# M3005.net
KiCad netlist of a schematic drawn in Altium Designer
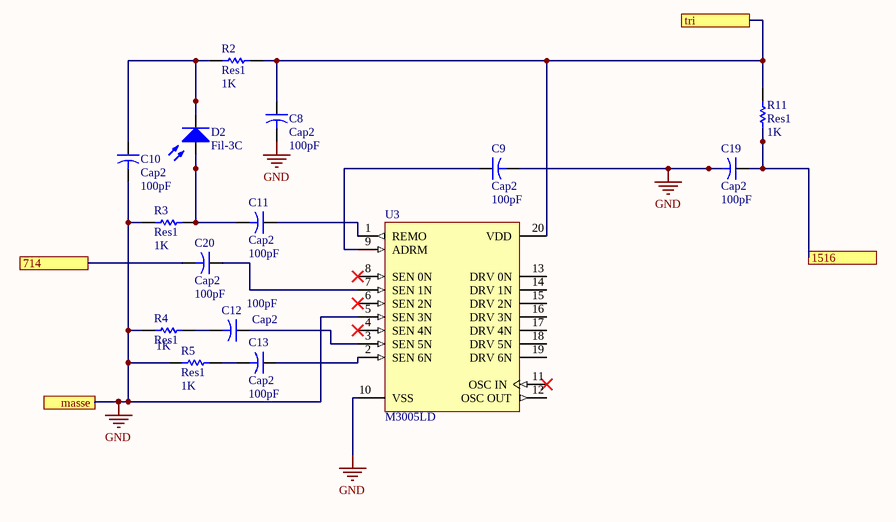
[diagram p0: M3005.SchDoc]

(export (version "E")
  (design (tool "Eeschema 10.0.6"))
  (components
    (comp (ref "C8")
      (value "Cap2")
      (footprint "RAD-0.2")
      (description "Capacitor")
      (fields (field (name "ALTIUM_VALUE") "100pF") (field (name "PUBLISHER") "Altium Limited"))
      (libsource (lib "Miscellaneous Devices") (part "Cap2"))
    )
    (comp (ref "C9")
      (value "Cap2")
      (footprint "RAD-0.2")
      (description "Capacitor")
      (fields (field (name "ALTIUM_VALUE") "100pF") (field (name "PUBLISHER") "Altium Limited"))
      (libsource (lib "Miscellaneous Devices") (part "Cap2"))
    )
    (comp (ref "C10")
      (value "Cap2")
      (footprint "RAD-0.2")
      (description "Capacitor")
      (fields (field (name "ALTIUM_VALUE") "100pF") (field (name "PUBLISHER") "Altium Limited"))
      (libsource (lib "Miscellaneous Devices") (part "Cap2"))
    )
    (comp (ref "C11")
      (value "Cap2")
      (footprint "RAD-0.2")
      (description "Capacitor")
      (fields (field (name "ALTIUM_VALUE") "100pF") (field (name "PUBLISHER") "Altium Limited"))
      (libsource (lib "Miscellaneous Devices") (part "Cap2"))
    )
    (comp (ref "C12")
      (value "Cap2")
      (footprint "RAD-0.2")
      (description "Capacitor")
      (fields (field (name "ALTIUM_VALUE") "100pF") (field (name "PUBLISHER") "Altium Limited"))
      (libsource (lib "Miscellaneous Devices") (part "Cap2"))
    )
    (comp (ref "C13")
      (value "Cap2")
      (footprint "RAD-0.2")
      (description "Capacitor")
      (fields (field (name "ALTIUM_VALUE") "100pF") (field (name "PUBLISHER") "Altium Limited"))
      (libsource (lib "Miscellaneous Devices") (part "Cap2"))
    )
    (comp (ref "C19")
      (value "Cap2")
      (footprint "RAD-0.2")
      (description "Capacitor")
      (fields (field (name "ALTIUM_VALUE") "100pF") (field (name "PUBLISHER") "Altium Limited"))
      (libsource (lib "Miscellaneous Devices") (part "Cap2"))
    )
    (comp (ref "C20")
      (value "Cap2")
      (footprint "RAD-0.2")
      (description "Capacitor")
      (fields (field (name "ALTIUM_VALUE") "100pF") (field (name "PUBLISHER") "Altium Limited"))
      (libsource (lib "Miscellaneous Devices") (part "Cap2"))
    )
    (comp (ref "D2")
      (value "Fil-3C")
      (footprint "PIN2")
      (description "Photosensitive Diode")
      (fields (field (name "PUBLISHER") "Altium Limited"))
      (libsource (lib "Miscellaneous Devices") (part "Photo Sen"))
    )
    (comp (ref "R2")
      (value "Res1")
      (footprint "AXIAL-0.3")
      (description "Resistor")
      (fields (field (name "ALTIUM_VALUE") "1K") (field (name "PUBLISHER") "Altium Limited"))
      (libsource (lib "Miscellaneous Devices") (part "Res1"))
    )
    (comp (ref "R3")
      (value "Res1")
      (footprint "AXIAL-0.3")
      (description "Resistor")
      (fields (field (name "ALTIUM_VALUE") "1K") (field (name "PUBLISHER") "Altium Limited"))
      (libsource (lib "Miscellaneous Devices") (part "Res1"))
    )
    (comp (ref "R4")
      (value "Res1")
      (footprint "AXIAL-0.3")
      (description "Resistor")
      (fields (field (name "ALTIUM_VALUE") "1K") (field (name "PUBLISHER") "Altium Limited"))
      (libsource (lib "Miscellaneous Devices") (part "Res1"))
    )
    (comp (ref "R5")
      (value "Res1")
      (footprint "AXIAL-0.3")
      (description "Resistor")
      (fields (field (name "ALTIUM_VALUE") "1K") (field (name "PUBLISHER") "Altium Limited"))
      (libsource (lib "Miscellaneous Devices") (part "Res1"))
    )
    (comp (ref "R11")
      (value "Res1")
      (footprint "AXIAL-0.3")
      (description "Resistor")
      (fields (field (name "ALTIUM_VALUE") "1K") (field (name "PUBLISHER") "Altium Limited"))
      (libsource (lib "Miscellaneous Devices") (part "Res1"))
    )
    (comp (ref "U3")
      (value "M3005LD")
      (footprint "SO20_N")
      (description "Remote Control Transmitter")
      (fields (field (name "PUBLISHER") "Altium Limited"))
      (libsource (lib "ST Remote Control Transmitter") (part "M3005LD"))
    )
  )
  (nets
    (net (code "1") (name "/714") (class "Default")
      (node (ref "C20") (pin "2") (pinfunction "2_2") (pintype "passive"))
    )
    (net (code "2") (name "/1516") (class "Default")
      (node (ref "C19") (pin "1") (pinfunction "1_1") (pintype "passive"))
      (node (ref "R11") (pin "1") (pinfunction "1_1") (pintype "passive"))
    )
    (net (code "3") (name "/tri") (class "Default")
      (node (ref "C8") (pin "1") (pinfunction "1_1") (pintype "passive"))
      (node (ref "R11") (pin "2") (pinfunction "2_2") (pintype "passive"))
      (node (ref "R2") (pin "1") (pinfunction "1_1") (pintype "passive"))
      (node (ref "U3") (pin "20") (pinfunction "VDD_20") (pintype "power_in"))
    )
    (net (code "4") (name "GND") (class "Default")
      (node (ref "C10") (pin "2") (pinfunction "2_2") (pintype "passive"))
      (node (ref "C19") (pin "2") (pinfunction "2_2") (pintype "passive"))
      (node (ref "C8") (pin "2") (pinfunction "2_2") (pintype "passive"))
      (node (ref "C9") (pin "2") (pinfunction "2_2") (pintype "passive"))
      (node (ref "R3") (pin "1") (pinfunction "1_1") (pintype "passive"))
      (node (ref "R4") (pin "1") (pinfunction "1_1") (pintype "passive"))
      (node (ref "R5") (pin "1") (pinfunction "1_1") (pintype "passive"))
      (node (ref "U3") (pin "10") (pinfunction "VSS_10") (pintype "power_in"))
      (node (ref "U3") (pin "5") (pinfunction "SEN_3N_5") (pintype "input"))
    )
    (net (code "5") (name "Net-(C12-Pad2)") (class "Default")
      (node (ref "C12") (pin "2") (pinfunction "2_2") (pintype "passive"))
      (node (ref "R4") (pin "2") (pinfunction "2_2") (pintype "passive"))
    )
    (net (code "6") (name "Net-(C13-Pad2)") (class "Default")
      (node (ref "C13") (pin "2") (pinfunction "2_2") (pintype "passive"))
      (node (ref "R5") (pin "2") (pinfunction "2_2") (pintype "passive"))
    )
    (net (code "7") (name "Net-(D2-A)") (class "Default")
      (node (ref "C11") (pin "2") (pinfunction "2_2") (pintype "passive"))
      (node (ref "D2") (pin "1") (pinfunction "A_1") (pintype "passive"))
      (node (ref "R3") (pin "2") (pinfunction "2_2") (pintype "passive"))
    )
    (net (code "8") (name "Net-(D2-K)") (class "Default")
      (node (ref "C10") (pin "1") (pinfunction "1_1") (pintype "passive"))
      (node (ref "D2") (pin "2") (pinfunction "K_2") (pintype "passive"))
      (node (ref "R2") (pin "2") (pinfunction "2_2") (pintype "passive"))
    )
    (net (code "9") (name "Net-(U3-ADRM)") (class "Default")
      (node (ref "C9") (pin "1") (pinfunction "1_1") (pintype "passive"))
      (node (ref "U3") (pin "9") (pinfunction "ADRM_9") (pintype "input"))
    )
    (net (code "10") (name "Net-(U3-REMO)") (class "Default")
      (node (ref "C11") (pin "1") (pinfunction "1_1") (pintype "passive"))
      (node (ref "U3") (pin "1") (pinfunction "REMO_1") (pintype "output"))
    )
    (net (code "11") (name "Net-(U3-SEN_1N)") (class "Default")
      (node (ref "C20") (pin "1") (pinfunction "1_1") (pintype "passive"))
      (node (ref "U3") (pin "7") (pinfunction "SEN_1N_7") (pintype "input"))
    )
    (net (code "12") (name "Net-(U3-SEN_5N)") (class "Default")
      (node (ref "C12") (pin "1") (pinfunction "1_1") (pintype "passive"))
      (node (ref "U3") (pin "3") (pinfunction "SEN_5N_3") (pintype "input"))
    )
    (net (code "13") (name "Net-(U3-SEN_6N)") (class "Default")
      (node (ref "C13") (pin "1") (pinfunction "1_1") (pintype "passive"))
      (node (ref "U3") (pin "2") (pinfunction "SEN_6N_2") (pintype "input"))
    )
    (net (code "14") (name "unconnected-(U3-DRV_0N-Pad13)") (class "Default")
      (node (ref "U3") (pin "13") (pinfunction "DRV_0N_13") (pintype "open_collector"))
    )
    (net (code "15") (name "unconnected-(U3-DRV_1N-Pad14)") (class "Default")
      (node (ref "U3") (pin "14") (pinfunction "DRV_1N_14") (pintype "open_collector"))
    )
    (net (code "16") (name "unconnected-(U3-DRV_2N-Pad15)") (class "Default")
      (node (ref "U3") (pin "15") (pinfunction "DRV_2N_15") (pintype "open_collector"))
    )
    (net (code "17") (name "unconnected-(U3-DRV_3N-Pad16)") (class "Default")
      (node (ref "U3") (pin "16") (pinfunction "DRV_3N_16") (pintype "open_collector"))
    )
    (net (code "18") (name "unconnected-(U3-DRV_4N-Pad17)") (class "Default")
      (node (ref "U3") (pin "17") (pinfunction "DRV_4N_17") (pintype "open_collector"))
    )
    (net (code "19") (name "unconnected-(U3-DRV_5N-Pad18)") (class "Default")
      (node (ref "U3") (pin "18") (pinfunction "DRV_5N_18") (pintype "open_collector"))
    )
    (net (code "20") (name "unconnected-(U3-DRV_6N-Pad19)") (class "Default")
      (node (ref "U3") (pin "19") (pinfunction "DRV_6N_19") (pintype "open_collector"))
    )
    (net (code "21") (name "unconnected-(U3-OSC_IN-Pad11)") (class "Default")
      (node (ref "U3") (pin "11") (pinfunction "OSC_IN_11") (pintype "input+no_connect"))
    )
    (net (code "22") (name "unconnected-(U3-OSC_OUT-Pad12)") (class "Default")
      (node (ref "U3") (pin "12") (pinfunction "OSC_OUT_12") (pintype "output"))
    )
    (net (code "23") (name "unconnected-(U3-SEN_0N-Pad8)") (class "Default")
      (node (ref "U3") (pin "8") (pinfunction "SEN_0N_8") (pintype "input+no_connect"))
    )
    (net (code "24") (name "unconnected-(U3-SEN_2N-Pad6)") (class "Default")
      (node (ref "U3") (pin "6") (pinfunction "SEN_2N_6") (pintype "input+no_connect"))
    )
    (net (code "25") (name "unconnected-(U3-SEN_4N-Pad4)") (class "Default")
      (node (ref "U3") (pin "4") (pinfunction "SEN_4N_4") (pintype "input+no_connect"))
    )
  )
)
